# ethernet_jack_cnc_shield_2_5.net
KiCad netlist of a schematic drawn in EAGLE
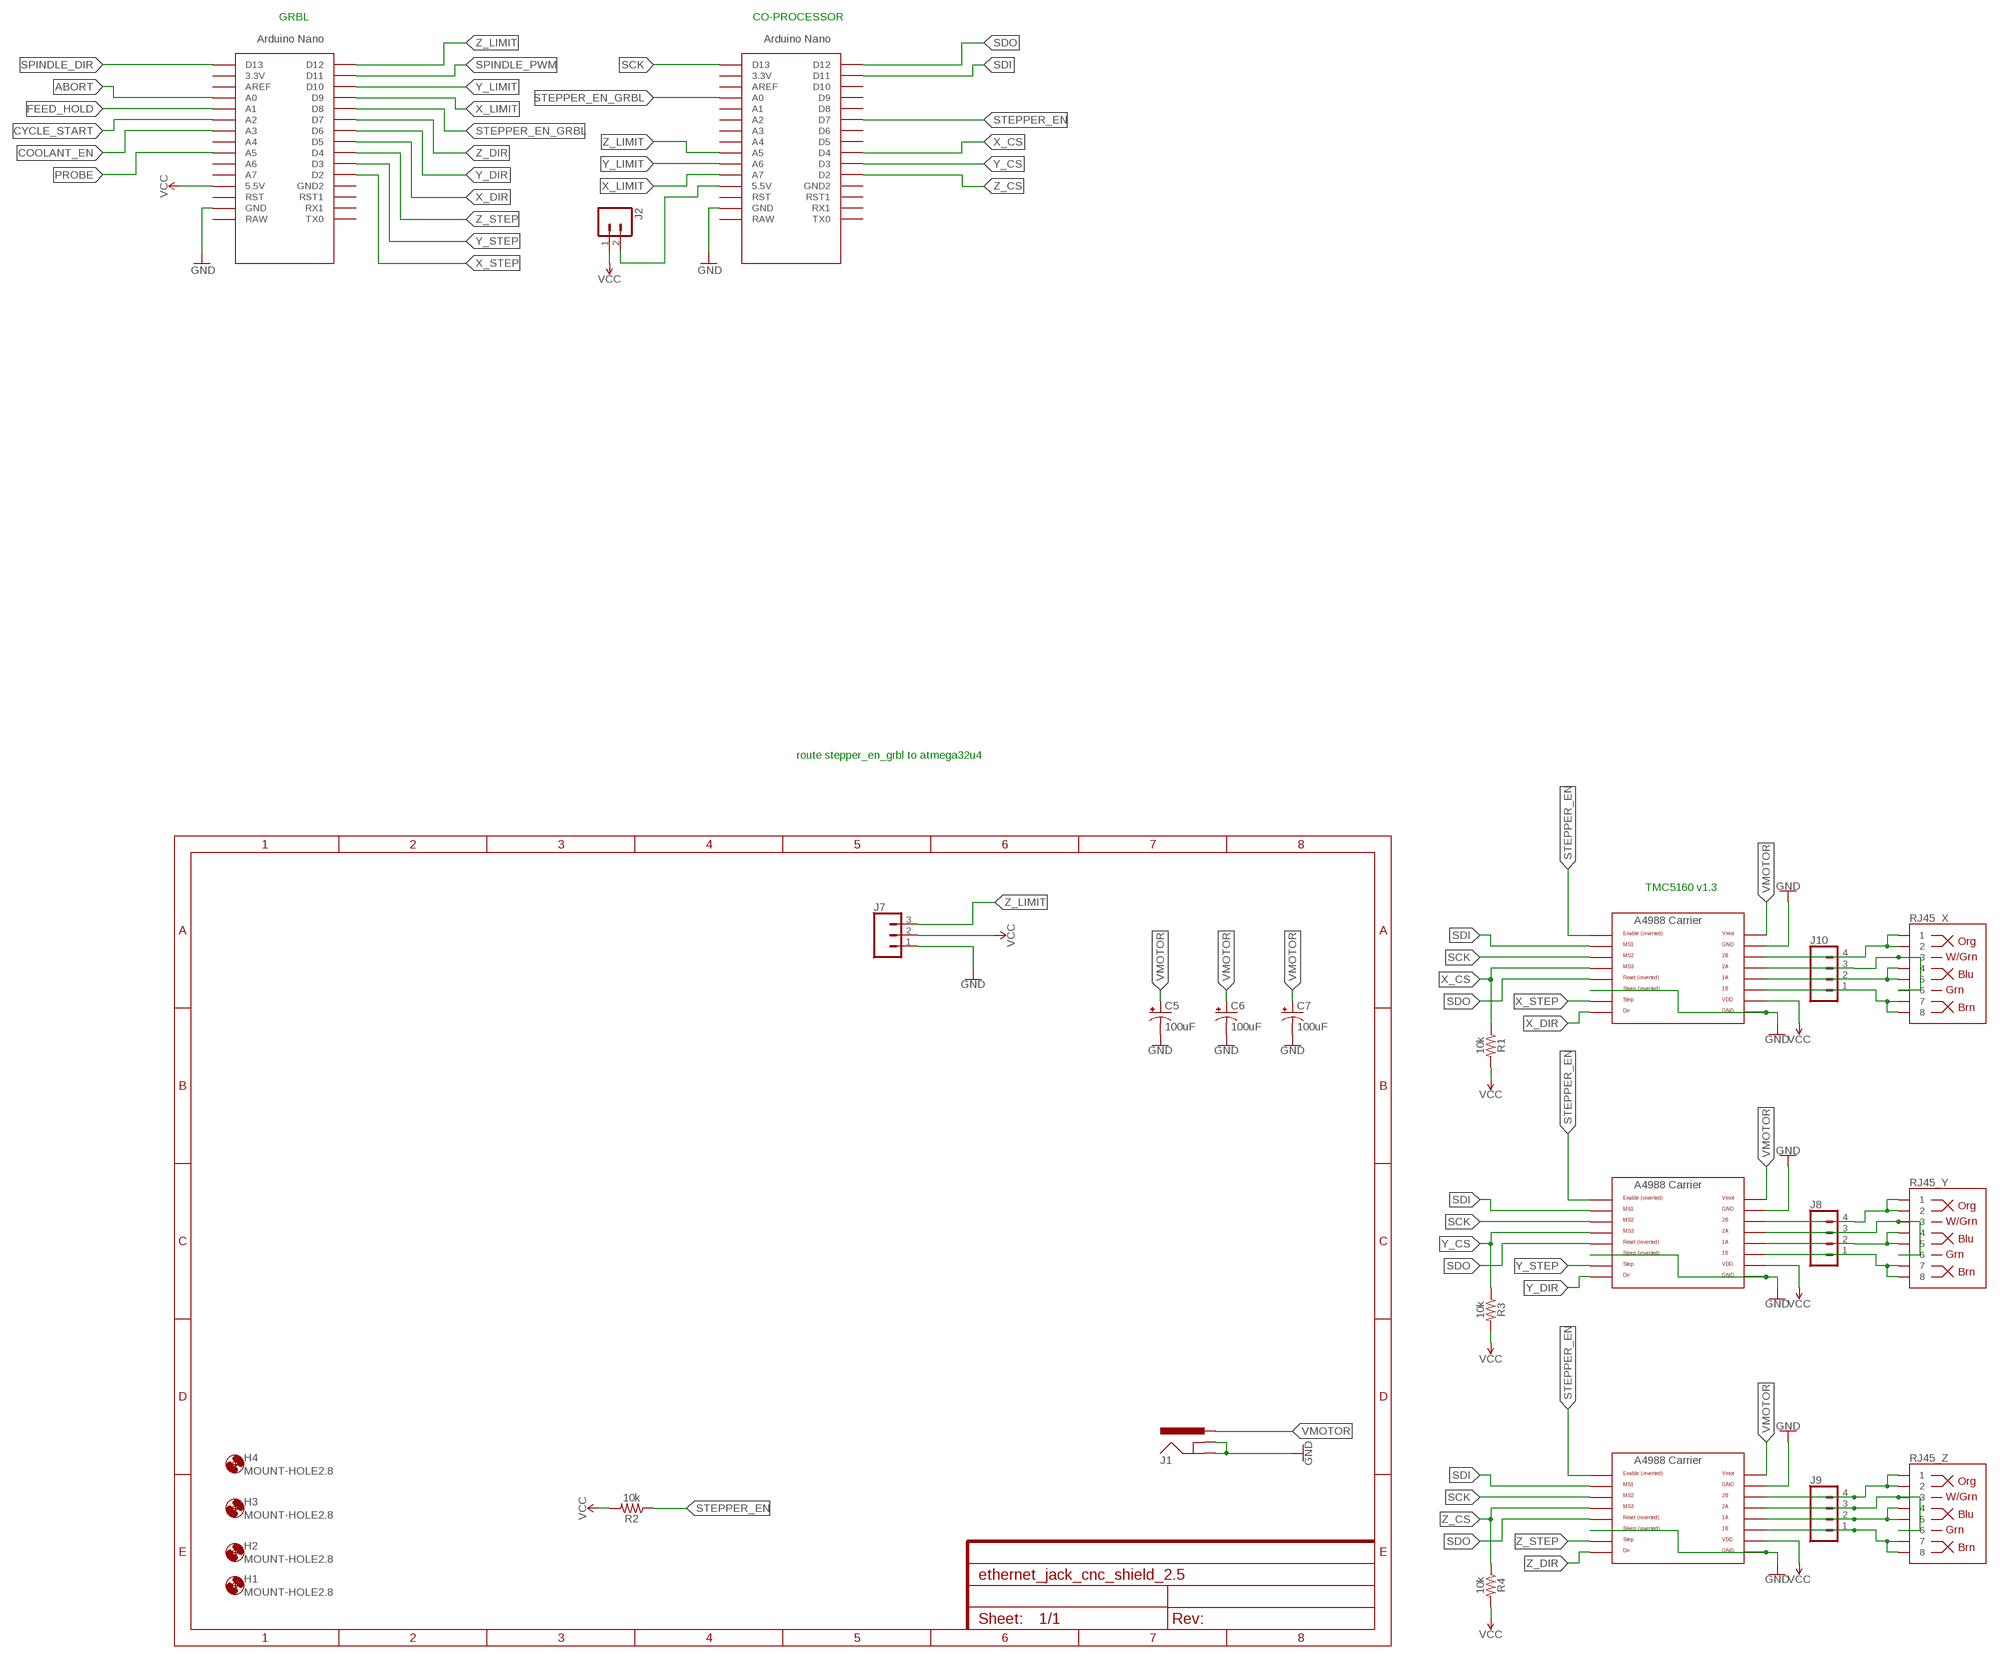
[diagram p0: schematic, sheet 1]

(export (version "E")
  (design (tool "Eeschema 10.0.6"))
  (components
    (comp (ref "C5")
      (value "100uF")
      (footprint "eagle-import:PANASONIC_D")
      (libsource (lib "eagle-import") (part "100UF-POLAR-25V-20%(ELEC)"))
    )
    (comp (ref "C6")
      (value "100uF")
      (footprint "eagle-import:PANASONIC_D")
      (libsource (lib "eagle-import") (part "100UF-POLAR-25V-20%(ELEC)"))
    )
    (comp (ref "C7")
      (value "100uF")
      (footprint "eagle-import:PANASONIC_D")
      (libsource (lib "eagle-import") (part "100UF-POLAR-25V-20%(ELEC)"))
    )
    (comp (ref "H1")
      (value "MOUNT-HOLE2.8")
      (footprint "eagle-import:2,8")
      (libsource (lib "eagle-import") (part "MOUNT-HOLE2.8"))
    )
    (comp (ref "H2")
      (value "MOUNT-HOLE2.8")
      (footprint "eagle-import:2,8")
      (libsource (lib "eagle-import") (part "MOUNT-HOLE2.8"))
    )
    (comp (ref "H3")
      (value "MOUNT-HOLE2.8")
      (footprint "eagle-import:2,8")
      (libsource (lib "eagle-import") (part "MOUNT-HOLE2.8"))
    )
    (comp (ref "H4")
      (value "MOUNT-HOLE2.8")
      (footprint "eagle-import:2,8")
      (libsource (lib "eagle-import") (part "MOUNT-HOLE2.8"))
    )
    (comp (ref "J1")
      (value "POWER_JACKPTH_BREAD")
      (footprint "eagle-import:POWER_JACK_PTH_BREAD")
      (libsource (lib "eagle-import") (part "POWER_JACKPTH_BREAD"))
    )
    (comp (ref "J2")
      (value "M02PTH")
      (footprint "eagle-import:1X02")
      (libsource (lib "eagle-import") (part "M02PTH"))
    )
    (comp (ref "J7")
      (value "CONN_03")
      (footprint "eagle-import:1X03")
      (libsource (lib "eagle-import") (part "CONN_03"))
    )
    (comp (ref "J8")
      (value "CONN_04")
      (footprint "eagle-import:1X04")
      (libsource (lib "eagle-import") (part "CONN_04"))
    )
    (comp (ref "J9")
      (value "CONN_04")
      (footprint "eagle-import:1X04")
      (libsource (lib "eagle-import") (part "CONN_04"))
    )
    (comp (ref "J10")
      (value "CONN_04")
      (footprint "eagle-import:1X04")
      (libsource (lib "eagle-import") (part "CONN_04"))
    )
    (comp (ref "R1")
      (value "10k")
      (footprint "eagle-import:1206")
      (libsource (lib "eagle-import") (part "RESISTOR1206"))
    )
    (comp (ref "R2")
      (value "10k")
      (footprint "eagle-import:1206")
      (libsource (lib "eagle-import") (part "RESISTOR1206"))
    )
    (comp (ref "R3")
      (value "10k")
      (footprint "eagle-import:1206")
      (libsource (lib "eagle-import") (part "RESISTOR1206"))
    )
    (comp (ref "R4")
      (value "10k")
      (footprint "eagle-import:1206")
      (libsource (lib "eagle-import") (part "RESISTOR1206"))
    )
    (comp (ref "RJ45_X")
      (value "RJ45")
      (footprint "eagle-import:RJ45-8")
      (libsource (lib "eagle-import") (part "RJ45-8"))
    )
    (comp (ref "RJ45_Y")
      (value "RJ45")
      (footprint "eagle-import:RJ45-8")
      (libsource (lib "eagle-import") (part "RJ45-8"))
    )
    (comp (ref "RJ45_Z")
      (value "RJ45")
      (footprint "eagle-import:RJ45-8")
      (libsource (lib "eagle-import") (part "RJ45-8"))
    )
    (comp (ref "U$2")
      (value "A4988BREAKOUT")
      (footprint "eagle-import:A4988BREAKOUT")
      (libsource (lib "eagle-import") (part "A4988BREAKOUT"))
    )
    (comp (ref "U$3")
      (value "A4988BREAKOUT")
      (footprint "eagle-import:A4988BREAKOUT")
      (libsource (lib "eagle-import") (part "A4988BREAKOUT"))
    )
    (comp (ref "U$4")
      (value "A4988BREAKOUT")
      (footprint "eagle-import:A4988BREAKOUT")
      (libsource (lib "eagle-import") (part "A4988BREAKOUT"))
    )
    (comp (ref "U$5")
      (value "NANO")
      (footprint "eagle-import:NANO")
      (libsource (lib "eagle-import") (part "NANO"))
    )
    (comp (ref "U$7")
      (value "NANO")
      (footprint "eagle-import:NANO")
      (libsource (lib "eagle-import") (part "NANO"))
    )
  )
  (nets
    (net (code "1") (name "ABORT") (class "Default")
      (node (ref "U$5") (pin "A0") (pinfunction "A0_A0") (pintype "bidirectional"))
    )
    (net (code "2") (name "COOLANT_EN") (class "Default")
      (node (ref "U$5") (pin "A3") (pinfunction "A3_A3") (pintype "bidirectional"))
    )
    (net (code "3") (name "CYCLE_START") (class "Default")
      (node (ref "U$5") (pin "A2") (pinfunction "A2_A2") (pintype "bidirectional"))
    )
    (net (code "4") (name "FEED_HOLD") (class "Default")
      (node (ref "U$5") (pin "A1") (pinfunction "A1_A1") (pintype "bidirectional"))
    )
    (net (code "5") (name "GND") (class "Default")
      (node (ref "C5") (pin "-") (pinfunction "-_-") (pintype "passive"))
      (node (ref "C6") (pin "-") (pinfunction "-_-") (pintype "passive"))
      (node (ref "C7") (pin "-") (pinfunction "-_-") (pintype "passive"))
      (node (ref "J1") (pin "GND") (pinfunction "GND_GND") (pintype "bidirectional"))
      (node (ref "J1") (pin "GNDBREAK") (pinfunction "GNDBREAK_GNDBREAK") (pintype "bidirectional"))
      (node (ref "J7") (pin "1") (pinfunction "1_1") (pintype "passive"))
      (node (ref "U$2") (pin "GND") (pinfunction "GND_GND") (pintype "power_in"))
      (node (ref "U$2") (pin "GND@0") (pinfunction "GND_GND@0") (pintype "power_in"))
      (node (ref "U$2") (pin "SLP") (pinfunction "SLEEP_SLP") (pintype "input"))
      (node (ref "U$3") (pin "GND") (pinfunction "GND_GND") (pintype "power_in"))
      (node (ref "U$3") (pin "GND@0") (pinfunction "GND_GND@0") (pintype "power_in"))
      (node (ref "U$3") (pin "SLP") (pinfunction "SLEEP_SLP") (pintype "input"))
      (node (ref "U$4") (pin "GND") (pinfunction "GND_GND") (pintype "power_in"))
      (node (ref "U$4") (pin "GND@0") (pinfunction "GND_GND@0") (pintype "power_in"))
      (node (ref "U$4") (pin "SLP") (pinfunction "SLEEP_SLP") (pintype "input"))
      (node (ref "U$5") (pin "GND") (pinfunction "GND_GND") (pintype "bidirectional"))
      (node (ref "U$7") (pin "GND") (pinfunction "GND_GND") (pintype "bidirectional"))
    )
    (net (code "6") (name "Net-(J8-Pad1)") (class "Default")
      (node (ref "J8") (pin "1") (pinfunction "1_1") (pintype "passive"))
      (node (ref "RJ45_Y") (pin "7") (pinfunction "7_7") (pintype "bidirectional"))
      (node (ref "RJ45_Y") (pin "8") (pinfunction "8_8") (pintype "bidirectional"))
      (node (ref "U$2") (pin "1B") (pinfunction "1B_1B") (pintype "output"))
    )
    (net (code "7") (name "Net-(J8-Pad2)") (class "Default")
      (node (ref "J8") (pin "2") (pinfunction "2_2") (pintype "passive"))
      (node (ref "RJ45_Y") (pin "4") (pinfunction "4_4") (pintype "bidirectional"))
      (node (ref "RJ45_Y") (pin "5") (pinfunction "5_5") (pintype "bidirectional"))
      (node (ref "U$2") (pin "1A") (pinfunction "1A_1A") (pintype "output"))
    )
    (net (code "8") (name "Net-(J8-Pad3)") (class "Default")
      (node (ref "J8") (pin "3") (pinfunction "3_3") (pintype "passive"))
      (node (ref "RJ45_Y") (pin "3") (pinfunction "3_3") (pintype "bidirectional"))
      (node (ref "RJ45_Y") (pin "6") (pinfunction "6_6") (pintype "bidirectional"))
      (node (ref "U$2") (pin "2A") (pinfunction "2A_2A") (pintype "output"))
    )
    (net (code "9") (name "Net-(J8-Pad4)") (class "Default")
      (node (ref "J8") (pin "4") (pinfunction "4_4") (pintype "passive"))
      (node (ref "RJ45_Y") (pin "1") (pinfunction "1_1") (pintype "bidirectional"))
      (node (ref "RJ45_Y") (pin "2") (pinfunction "2_2") (pintype "bidirectional"))
      (node (ref "U$2") (pin "2B") (pinfunction "2B_2B") (pintype "output"))
    )
    (net (code "10") (name "Net-(J9-Pad1)") (class "Default")
      (node (ref "J9") (pin "1") (pinfunction "1_1") (pintype "passive"))
      (node (ref "RJ45_Z") (pin "7") (pinfunction "7_7") (pintype "bidirectional"))
      (node (ref "RJ45_Z") (pin "8") (pinfunction "8_8") (pintype "bidirectional"))
      (node (ref "U$3") (pin "1B") (pinfunction "1B_1B") (pintype "output"))
    )
    (net (code "11") (name "Net-(J9-Pad2)") (class "Default")
      (node (ref "J9") (pin "2") (pinfunction "2_2") (pintype "passive"))
      (node (ref "RJ45_Z") (pin "4") (pinfunction "4_4") (pintype "bidirectional"))
      (node (ref "RJ45_Z") (pin "5") (pinfunction "5_5") (pintype "bidirectional"))
      (node (ref "U$3") (pin "1A") (pinfunction "1A_1A") (pintype "output"))
    )
    (net (code "12") (name "Net-(J9-Pad3)") (class "Default")
      (node (ref "J9") (pin "3") (pinfunction "3_3") (pintype "passive"))
      (node (ref "RJ45_Z") (pin "3") (pinfunction "3_3") (pintype "bidirectional"))
      (node (ref "RJ45_Z") (pin "6") (pinfunction "6_6") (pintype "bidirectional"))
      (node (ref "U$3") (pin "2A") (pinfunction "2A_2A") (pintype "output"))
    )
    (net (code "13") (name "Net-(J9-Pad4)") (class "Default")
      (node (ref "J9") (pin "4") (pinfunction "4_4") (pintype "passive"))
      (node (ref "RJ45_Z") (pin "1") (pinfunction "1_1") (pintype "bidirectional"))
      (node (ref "RJ45_Z") (pin "2") (pinfunction "2_2") (pintype "bidirectional"))
      (node (ref "U$3") (pin "2B") (pinfunction "2B_2B") (pintype "output"))
    )
    (net (code "14") (name "Net-(J10-Pad1)") (class "Default")
      (node (ref "J10") (pin "1") (pinfunction "1_1") (pintype "passive"))
      (node (ref "RJ45_X") (pin "7") (pinfunction "7_7") (pintype "bidirectional"))
      (node (ref "RJ45_X") (pin "8") (pinfunction "8_8") (pintype "bidirectional"))
      (node (ref "U$4") (pin "1B") (pinfunction "1B_1B") (pintype "output"))
    )
    (net (code "15") (name "Net-(J10-Pad2)") (class "Default")
      (node (ref "J10") (pin "2") (pinfunction "2_2") (pintype "passive"))
      (node (ref "RJ45_X") (pin "4") (pinfunction "4_4") (pintype "bidirectional"))
      (node (ref "RJ45_X") (pin "5") (pinfunction "5_5") (pintype "bidirectional"))
      (node (ref "U$4") (pin "1A") (pinfunction "1A_1A") (pintype "output"))
    )
    (net (code "16") (name "Net-(J10-Pad3)") (class "Default")
      (node (ref "J10") (pin "3") (pinfunction "3_3") (pintype "passive"))
      (node (ref "RJ45_X") (pin "3") (pinfunction "3_3") (pintype "bidirectional"))
      (node (ref "RJ45_X") (pin "6") (pinfunction "6_6") (pintype "bidirectional"))
      (node (ref "U$4") (pin "2A") (pinfunction "2A_2A") (pintype "output"))
    )
    (net (code "17") (name "Net-(J10-Pad4)") (class "Default")
      (node (ref "J10") (pin "4") (pinfunction "4_4") (pintype "passive"))
      (node (ref "RJ45_X") (pin "1") (pinfunction "1_1") (pintype "bidirectional"))
      (node (ref "RJ45_X") (pin "2") (pinfunction "2_2") (pintype "bidirectional"))
      (node (ref "U$4") (pin "2B") (pinfunction "2B_2B") (pintype "output"))
    )
    (net (code "18") (name "Net-(U$7-5.5V)") (class "Default")
      (node (ref "J2") (pin "2") (pinfunction "2_2") (pintype "passive"))
      (node (ref "U$7") (pin "5V") (pinfunction "5.5V_5V") (pintype "bidirectional"))
    )
    (net (code "19") (name "PROBE") (class "Default")
      (node (ref "U$5") (pin "A5") (pinfunction "A5_A5") (pintype "bidirectional"))
    )
    (net (code "20") (name "SCK") (class "Default")
      (node (ref "U$2") (pin "MS2") (pinfunction "MS2_MS2") (pintype "input"))
      (node (ref "U$3") (pin "MS2") (pinfunction "MS2_MS2") (pintype "input"))
      (node (ref "U$4") (pin "MS2") (pinfunction "MS2_MS2") (pintype "input"))
      (node (ref "U$7") (pin "D13") (pinfunction "D13_D13") (pintype "bidirectional"))
    )
    (net (code "21") (name "SDI") (class "Default")
      (node (ref "U$2") (pin "MS1") (pinfunction "MS1_MS1") (pintype "input"))
      (node (ref "U$3") (pin "MS1") (pinfunction "MS1_MS1") (pintype "input"))
      (node (ref "U$4") (pin "MS1") (pinfunction "MS1_MS1") (pintype "input"))
      (node (ref "U$7") (pin "D11") (pinfunction "D11_D11") (pintype "bidirectional"))
    )
    (net (code "22") (name "SDO") (class "Default")
      (node (ref "U$2") (pin "RST") (pinfunction "RST_RST") (pintype "input"))
      (node (ref "U$3") (pin "RST") (pinfunction "RST_RST") (pintype "input"))
      (node (ref "U$4") (pin "RST") (pinfunction "RST_RST") (pintype "input"))
      (node (ref "U$7") (pin "D12") (pinfunction "D12_D12") (pintype "bidirectional"))
    )
    (net (code "23") (name "SPINDLE_DIR") (class "Default")
      (node (ref "U$5") (pin "D13") (pinfunction "D13_D13") (pintype "bidirectional"))
    )
    (net (code "24") (name "SPINDLE_PWM") (class "Default")
      (node (ref "U$5") (pin "D11") (pinfunction "D11_D11") (pintype "bidirectional"))
    )
    (net (code "25") (name "STEPPER_EN") (class "Default")
      (node (ref "R2") (pin "1") (pinfunction "1_1") (pintype "passive"))
      (node (ref "U$2") (pin "EN") (pinfunction "EN_EN") (pintype "input"))
      (node (ref "U$3") (pin "EN") (pinfunction "EN_EN") (pintype "input"))
      (node (ref "U$4") (pin "EN") (pinfunction "EN_EN") (pintype "input"))
      (node (ref "U$7") (pin "D7") (pinfunction "D7_D7") (pintype "bidirectional"))
    )
    (net (code "26") (name "STEPPER_EN_GRBL") (class "Default")
      (node (ref "U$5") (pin "D8") (pinfunction "D8_D8") (pintype "bidirectional"))
      (node (ref "U$7") (pin "A0") (pinfunction "A0_A0") (pintype "bidirectional"))
    )
    (net (code "27") (name "VCC") (class "Default")
      (node (ref "J2") (pin "1") (pinfunction "1_1") (pintype "passive"))
      (node (ref "J7") (pin "2") (pinfunction "2_2") (pintype "passive"))
      (node (ref "R1") (pin "2") (pinfunction "2_2") (pintype "passive"))
      (node (ref "R2") (pin "2") (pinfunction "2_2") (pintype "passive"))
      (node (ref "R3") (pin "2") (pinfunction "2_2") (pintype "passive"))
      (node (ref "R4") (pin "2") (pinfunction "2_2") (pintype "passive"))
      (node (ref "U$2") (pin "VDD") (pinfunction "VDD_VDD") (pintype "power_in"))
      (node (ref "U$3") (pin "VDD") (pinfunction "VDD_VDD") (pintype "power_in"))
      (node (ref "U$4") (pin "VDD") (pinfunction "VDD_VDD") (pintype "power_in"))
      (node (ref "U$5") (pin "5V") (pinfunction "5.5V_5V") (pintype "bidirectional"))
    )
    (net (code "28") (name "VMOTOR") (class "Default")
      (node (ref "C5") (pin "+") (pinfunction "+_+") (pintype "passive"))
      (node (ref "C6") (pin "+") (pinfunction "+_+") (pintype "passive"))
      (node (ref "C7") (pin "+") (pinfunction "+_+") (pintype "passive"))
      (node (ref "J1") (pin "PWR") (pinfunction "PWR_PWR") (pintype "bidirectional"))
      (node (ref "U$2") (pin "VMOT") (pinfunction "VMOT_VMOT") (pintype "power_in"))
      (node (ref "U$3") (pin "VMOT") (pinfunction "VMOT_VMOT") (pintype "power_in"))
      (node (ref "U$4") (pin "VMOT") (pinfunction "VMOT_VMOT") (pintype "power_in"))
    )
    (net (code "29") (name "X_CS") (class "Default")
      (node (ref "R1") (pin "1") (pinfunction "1_1") (pintype "passive"))
      (node (ref "U$4") (pin "MS3") (pinfunction "MS3_MS3") (pintype "input"))
      (node (ref "U$7") (pin "D4") (pinfunction "D4_D4") (pintype "bidirectional"))
    )
    (net (code "30") (name "X_DIR") (class "Default")
      (node (ref "U$4") (pin "DIR") (pinfunction "DIR_DIR") (pintype "input"))
      (node (ref "U$5") (pin "D5") (pinfunction "D5_D5") (pintype "bidirectional"))
    )
    (net (code "31") (name "X_LIMIT") (class "Default")
      (node (ref "U$5") (pin "D9") (pinfunction "D9_D9") (pintype "bidirectional"))
      (node (ref "U$7") (pin "A7") (pinfunction "A7_A7") (pintype "bidirectional"))
    )
    (net (code "32") (name "X_STEP") (class "Default")
      (node (ref "U$4") (pin "STEP") (pinfunction "STEP_STEP") (pintype "input"))
      (node (ref "U$5") (pin "D2") (pinfunction "D2_D2") (pintype "bidirectional"))
    )
    (net (code "33") (name "Y_CS") (class "Default")
      (node (ref "R3") (pin "1") (pinfunction "1_1") (pintype "passive"))
      (node (ref "U$2") (pin "MS3") (pinfunction "MS3_MS3") (pintype "input"))
      (node (ref "U$7") (pin "D3") (pinfunction "D3_D3") (pintype "bidirectional"))
    )
    (net (code "34") (name "Y_DIR") (class "Default")
      (node (ref "U$2") (pin "DIR") (pinfunction "DIR_DIR") (pintype "input"))
      (node (ref "U$5") (pin "D6") (pinfunction "D6_D6") (pintype "bidirectional"))
    )
    (net (code "35") (name "Y_LIMIT") (class "Default")
      (node (ref "U$5") (pin "D10") (pinfunction "D10_D10") (pintype "bidirectional"))
      (node (ref "U$7") (pin "A6") (pinfunction "A6_A6") (pintype "bidirectional"))
    )
    (net (code "36") (name "Y_STEP") (class "Default")
      (node (ref "U$2") (pin "STEP") (pinfunction "STEP_STEP") (pintype "input"))
      (node (ref "U$5") (pin "D3") (pinfunction "D3_D3") (pintype "bidirectional"))
    )
    (net (code "37") (name "Z_CS") (class "Default")
      (node (ref "R4") (pin "1") (pinfunction "1_1") (pintype "passive"))
      (node (ref "U$3") (pin "MS3") (pinfunction "MS3_MS3") (pintype "input"))
      (node (ref "U$7") (pin "D2") (pinfunction "D2_D2") (pintype "bidirectional"))
    )
    (net (code "38") (name "Z_DIR") (class "Default")
      (node (ref "U$3") (pin "DIR") (pinfunction "DIR_DIR") (pintype "input"))
      (node (ref "U$5") (pin "D7") (pinfunction "D7_D7") (pintype "bidirectional"))
    )
    (net (code "39") (name "Z_LIMIT") (class "Default")
      (node (ref "J7") (pin "3") (pinfunction "3_3") (pintype "passive"))
      (node (ref "U$5") (pin "D12") (pinfunction "D12_D12") (pintype "bidirectional"))
      (node (ref "U$7") (pin "A5") (pinfunction "A5_A5") (pintype "bidirectional"))
    )
    (net (code "40") (name "Z_STEP") (class "Default")
      (node (ref "U$3") (pin "STEP") (pinfunction "STEP_STEP") (pintype "input"))
      (node (ref "U$5") (pin "D4") (pinfunction "D4_D4") (pintype "bidirectional"))
    )
    (net (code "41") (name "unconnected-(U$5-GND2-PadGND1)") (class "Default")
      (node (ref "U$5") (pin "GND1") (pinfunction "GND2_GND1") (pintype "bidirectional"))
    )
    (net (code "42") (name "unconnected-(U$5-Pad3.3V)") (class "Default")
      (node (ref "U$5") (pin "3.3V") (pinfunction "3.3V_3.3V") (pintype "bidirectional"))
    )
    (net (code "43") (name "unconnected-(U$5-PadA4)") (class "Default")
      (node (ref "U$5") (pin "A4") (pinfunction "A4_A4") (pintype "bidirectional"))
    )
    (net (code "44") (name "unconnected-(U$5-PadA6)") (class "Default")
      (node (ref "U$5") (pin "A6") (pinfunction "A6_A6") (pintype "bidirectional"))
    )
    (net (code "45") (name "unconnected-(U$5-PadA7)") (class "Default")
      (node (ref "U$5") (pin "A7") (pinfunction "A7_A7") (pintype "bidirectional"))
    )
    (net (code "46") (name "unconnected-(U$5-PadAREF)") (class "Default")
      (node (ref "U$5") (pin "AREF") (pinfunction "AREF_AREF") (pintype "bidirectional"))
    )
    (net (code "47") (name "unconnected-(U$5-PadICSP1)") (class "Default")
      (node (ref "U$5") (pin "ICSP1") (pinfunction "ICSP1_ICSP1") (pintype "bidirectional"))
    )
    (net (code "48") (name "unconnected-(U$5-PadICSP2)") (class "Default")
      (node (ref "U$5") (pin "ICSP2") (pinfunction "ICSP2_ICSP2") (pintype "bidirectional"))
    )
    (net (code "49") (name "unconnected-(U$5-PadICSP3)") (class "Default")
      (node (ref "U$5") (pin "ICSP3") (pinfunction "ICSP3_ICSP3") (pintype "bidirectional"))
    )
    (net (code "50") (name "unconnected-(U$5-PadICSP4)") (class "Default")
      (node (ref "U$5") (pin "ICSP4") (pinfunction "ICSP4_ICSP4") (pintype "bidirectional"))
    )
    (net (code "51") (name "unconnected-(U$5-PadICSP5)") (class "Default")
      (node (ref "U$5") (pin "ICSP5") (pinfunction "ICSP5_ICSP5") (pintype "bidirectional"))
    )
    (net (code "52") (name "unconnected-(U$5-PadICSP6)") (class "Default")
      (node (ref "U$5") (pin "ICSP6") (pinfunction "ICSP6_ICSP6") (pintype "bidirectional"))
    )
    (net (code "53") (name "unconnected-(U$5-PadRAW)") (class "Default")
      (node (ref "U$5") (pin "RAW") (pinfunction "RAW_RAW") (pintype "bidirectional"))
    )
    (net (code "54") (name "unconnected-(U$5-PadRST)") (class "Default")
      (node (ref "U$5") (pin "RST") (pinfunction "RST_RST") (pintype "bidirectional"))
    )
    (net (code "55") (name "unconnected-(U$5-PadRST1)") (class "Default")
      (node (ref "U$5") (pin "RST1") (pinfunction "RST1_RST1") (pintype "bidirectional"))
    )
    (net (code "56") (name "unconnected-(U$5-PadRX1)") (class "Default")
      (node (ref "U$5") (pin "RX1") (pinfunction "RX1_RX1") (pintype "bidirectional"))
    )
    (net (code "57") (name "unconnected-(U$5-PadTX0)") (class "Default")
      (node (ref "U$5") (pin "TX0") (pinfunction "TX0_TX0") (pintype "bidirectional"))
    )
    (net (code "58") (name "unconnected-(U$7-GND2-PadGND1)") (class "Default")
      (node (ref "U$7") (pin "GND1") (pinfunction "GND2_GND1") (pintype "bidirectional"))
    )
    (net (code "59") (name "unconnected-(U$7-Pad3.3V)") (class "Default")
      (node (ref "U$7") (pin "3.3V") (pinfunction "3.3V_3.3V") (pintype "bidirectional"))
    )
    (net (code "60") (name "unconnected-(U$7-PadA1)") (class "Default")
      (node (ref "U$7") (pin "A1") (pinfunction "A1_A1") (pintype "bidirectional"))
    )
    (net (code "61") (name "unconnected-(U$7-PadA2)") (class "Default")
      (node (ref "U$7") (pin "A2") (pinfunction "A2_A2") (pintype "bidirectional"))
    )
    (net (code "62") (name "unconnected-(U$7-PadA3)") (class "Default")
      (node (ref "U$7") (pin "A3") (pinfunction "A3_A3") (pintype "bidirectional"))
    )
    (net (code "63") (name "unconnected-(U$7-PadA4)") (class "Default")
      (node (ref "U$7") (pin "A4") (pinfunction "A4_A4") (pintype "bidirectional"))
    )
    (net (code "64") (name "unconnected-(U$7-PadAREF)") (class "Default")
      (node (ref "U$7") (pin "AREF") (pinfunction "AREF_AREF") (pintype "bidirectional"))
    )
    (net (code "65") (name "unconnected-(U$7-PadD5)") (class "Default")
      (node (ref "U$7") (pin "D5") (pinfunction "D5_D5") (pintype "bidirectional"))
    )
    (net (code "66") (name "unconnected-(U$7-PadD6)") (class "Default")
      (node (ref "U$7") (pin "D6") (pinfunction "D6_D6") (pintype "bidirectional"))
    )
    (net (code "67") (name "unconnected-(U$7-PadD8)") (class "Default")
      (node (ref "U$7") (pin "D8") (pinfunction "D8_D8") (pintype "bidirectional"))
    )
    (net (code "68") (name "unconnected-(U$7-PadD9)") (class "Default")
      (node (ref "U$7") (pin "D9") (pinfunction "D9_D9") (pintype "bidirectional"))
    )
    (net (code "69") (name "unconnected-(U$7-PadD10)") (class "Default")
      (node (ref "U$7") (pin "D10") (pinfunction "D10_D10") (pintype "bidirectional"))
    )
    (net (code "70") (name "unconnected-(U$7-PadICSP1)") (class "Default")
      (node (ref "U$7") (pin "ICSP1") (pinfunction "ICSP1_ICSP1") (pintype "bidirectional"))
    )
    (net (code "71") (name "unconnected-(U$7-PadICSP2)") (class "Default")
      (node (ref "U$7") (pin "ICSP2") (pinfunction "ICSP2_ICSP2") (pintype "bidirectional"))
    )
    (net (code "72") (name "unconnected-(U$7-PadICSP3)") (class "Default")
      (node (ref "U$7") (pin "ICSP3") (pinfunction "ICSP3_ICSP3") (pintype "bidirectional"))
    )
    (net (code "73") (name "unconnected-(U$7-PadICSP4)") (class "Default")
      (node (ref "U$7") (pin "ICSP4") (pinfunction "ICSP4_ICSP4") (pintype "bidirectional"))
    )
    (net (code "74") (name "unconnected-(U$7-PadICSP5)") (class "Default")
      (node (ref "U$7") (pin "ICSP5") (pinfunction "ICSP5_ICSP5") (pintype "bidirectional"))
    )
    (net (code "75") (name "unconnected-(U$7-PadICSP6)") (class "Default")
      (node (ref "U$7") (pin "ICSP6") (pinfunction "ICSP6_ICSP6") (pintype "bidirectional"))
    )
    (net (code "76") (name "unconnected-(U$7-PadRAW)") (class "Default")
      (node (ref "U$7") (pin "RAW") (pinfunction "RAW_RAW") (pintype "bidirectional"))
    )
    (net (code "77") (name "unconnected-(U$7-PadRST)") (class "Default")
      (node (ref "U$7") (pin "RST") (pinfunction "RST_RST") (pintype "bidirectional"))
    )
    (net (code "78") (name "unconnected-(U$7-PadRST1)") (class "Default")
      (node (ref "U$7") (pin "RST1") (pinfunction "RST1_RST1") (pintype "bidirectional"))
    )
    (net (code "79") (name "unconnected-(U$7-PadRX1)") (class "Default")
      (node (ref "U$7") (pin "RX1") (pinfunction "RX1_RX1") (pintype "bidirectional"))
    )
    (net (code "80") (name "unconnected-(U$7-PadTX0)") (class "Default")
      (node (ref "U$7") (pin "TX0") (pinfunction "TX0_TX0") (pintype "bidirectional"))
    )
  )
)
